# L002-Square-Schematic.net
KiCad netlist of a schematic drawn in EAGLE
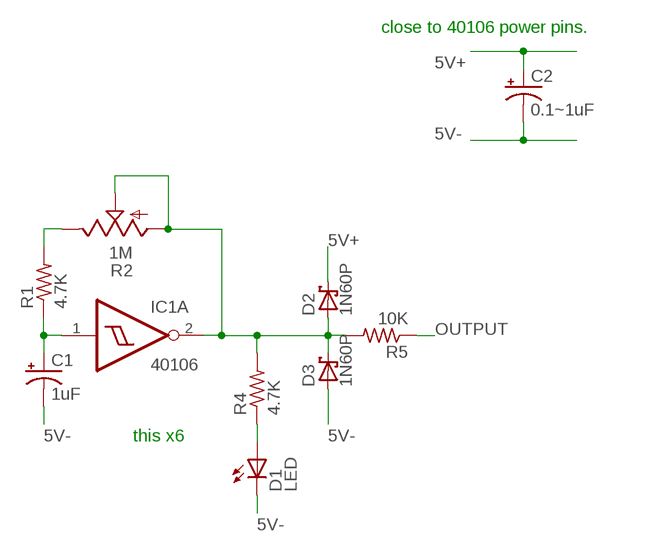
[diagram p0: schematic, sheet 1]

(export (version "E")
  (design (tool "Eeschema 10.0.6"))
  (components
    (comp (ref "C1")
      (value "1uF")
      (footprint "eagle-import:E2,5-6")
      (libsource (lib "eagle-import") (part "CPOL-USE2.5-6"))
    )
    (comp (ref "C2")
      (value "0.1~1uF")
      (footprint "eagle-import:E2,5-6")
      (libsource (lib "eagle-import") (part "CPOL-USE2.5-6"))
    )
    (comp (ref "D1")
      (value "LED")
      (footprint "eagle-import:SFH482")
      (libsource (lib "eagle-import") (part "SFH482"))
    )
    (comp (ref "D2")
      (value "1N60P")
      (footprint "eagle-import:DO41-7.6")
      (libsource (lib "eagle-import") (part "1N5817-B"))
    )
    (comp (ref "D3")
      (value "1N60P")
      (footprint "eagle-import:DO41-7.6")
      (libsource (lib "eagle-import") (part "1N5817-B"))
    )
    (comp (ref "IC1")
      (value "40106")
      (footprint "eagle-import:DIL14")
      (libsource (lib "eagle-import") (part "40106N"))
    )
    (comp (ref "R1")
      (value "4.7K")
      (footprint "eagle-import:VMTA55")
      (libsource (lib "eagle-import") (part "R-US_VMTA55"))
    )
    (comp (ref "R2")
      (value "1M")
      (footprint "eagle-import:EVUFXM")
      (libsource (lib "eagle-import") (part "US-EVUMF3"))
    )
    (comp (ref "R4")
      (value "4.7K")
      (footprint "eagle-import:VMTA55")
      (libsource (lib "eagle-import") (part "R-US_VMTA55"))
    )
    (comp (ref "R5")
      (value "10K")
      (footprint "eagle-import:VMTA55")
      (libsource (lib "eagle-import") (part "R-US_VMTA55"))
    )
  )
  (nets
    (net (code "1") (name "/5V+") (class "Default")
      (node (ref "C2") (pin "+") (pinfunction "+_+") (pintype "passive"))
      (node (ref "D2") (pin "C") (pinfunction "C_C") (pintype "passive"))
    )
    (net (code "2") (name "/5V-") (class "Default")
      (node (ref "C1") (pin "-") (pinfunction "-_-") (pintype "passive"))
      (node (ref "C2") (pin "-") (pinfunction "-_-") (pintype "passive"))
      (node (ref "D1") (pin "K") (pinfunction "C_K") (pintype "passive"))
      (node (ref "D3") (pin "A") (pinfunction "A_A") (pintype "passive"))
    )
    (net (code "3") (name "/OUTPUT") (class "Default")
      (node (ref "D2") (pin "A") (pinfunction "A_A") (pintype "passive"))
      (node (ref "D3") (pin "C") (pinfunction "C_C") (pintype "passive"))
      (node (ref "IC1") (pin "2") (pinfunction "O_2") (pintype "output"))
      (node (ref "R2") (pin "1") (pinfunction "A_1") (pintype "passive"))
      (node (ref "R2") (pin "2") (pinfunction "S_2") (pintype "passive"))
      (node (ref "R4") (pin "2") (pinfunction "2_2") (pintype "passive"))
      (node (ref "R5") (pin "1") (pinfunction "1_1") (pintype "passive"))
      (node (ref "R5") (pin "2") (pinfunction "2_2") (pintype "passive"))
    )
    (net (code "4") (name "Net-(D1-PadA)") (class "Default")
      (node (ref "D1") (pin "A") (pinfunction "A_A") (pintype "passive"))
      (node (ref "R4") (pin "1") (pinfunction "1_1") (pintype "passive"))
    )
    (net (code "5") (name "Net-(IC1A-I)") (class "Default")
      (node (ref "C1") (pin "+") (pinfunction "+_+") (pintype "passive"))
      (node (ref "IC1") (pin "1") (pinfunction "I_1") (pintype "input"))
      (node (ref "R1") (pin "1") (pinfunction "1_1") (pintype "passive"))
    )
    (net (code "6") (name "Net-(R2-E)") (class "Default")
      (node (ref "R1") (pin "2") (pinfunction "2_2") (pintype "passive"))
      (node (ref "R2") (pin "3") (pinfunction "E_3") (pintype "passive"))
    )
  )
)
